# Filter-13.net
KiCad netlist of a schematic drawn in Altium Designer
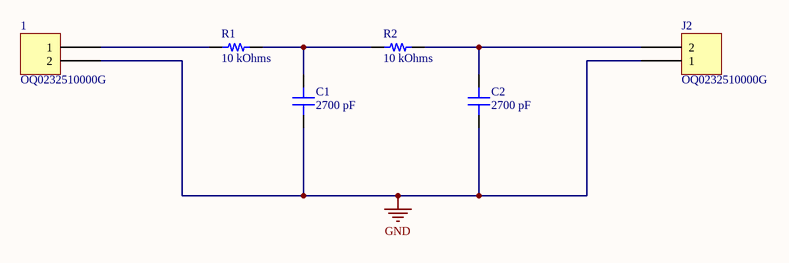
[diagram p0: Filter-13.SchDoc]

(export (version "E")
  (design (tool "Eeschema 10.0.6"))
  (components
    (comp (ref "1")
      (value "OQ0232510000G")
      (footprint "FCI 06-381-2PIN")
      (description "TERM BLOCK HDR 2POS 90DEG 3.81MM")
      (fields (field (name "MANUFACTURER") "Amphenol Anytek"))
      (libsource (lib "") (part "2 Pin_1"))
    )
    (comp (ref "C1")
      (value "2700 pF")
      (footprint "CAP 0603_1608")
      (description "CAP CER 2700PF 25V NP0 0603")
      (fields (field (name "PART NUMBER") "C0603C272F3GAC7867") (field (name "MANUFACTURER") "KEMET"))
      (libsource (lib "Celestial Altium Library - altium_library") (part "Capacitor"))
    )
    (comp (ref "C2")
      (value "2700 pF")
      (footprint "CAP 0603_1608")
      (description "CAP CER 2700PF 25V NP0 0603")
      (fields (field (name "PART NUMBER") "C0603C272F3GAC7867") (field (name "MANUFACTURER") "KEMET"))
      (libsource (lib "Celestial Altium Library - altium_library") (part "Capacitor"))
    )
    (comp (ref "J2")
      (value "OQ0232510000G")
      (footprint "FCI 06-381-2PIN")
      (description "TERM BLOCK HDR 2POS 90DEG 3.81MM")
      (fields (field (name "MANUFACTURER") "Amphenol Anytek"))
      (libsource (lib "Celestial Altium Library - altium_library") (part "2 Pin"))
    )
    (comp (ref "R1")
      (value "10 kOhms")
      (footprint "RES 0603_1608")
      (description "RES 10K OHM 0.1% 1/16W 0603")
      (fields
        (field (name "PART NUMBER") "RNCS0603BKE10K0")
        (field (name "MANUFACTURER") "Stackpole Electronics Inc")
      )
      (libsource (lib "Celestial Altium Library - altium_library") (part "Resistor"))
    )
    (comp (ref "R2")
      (value "10 kOhms")
      (footprint "RES 0603_1608")
      (description "RES 10K OHM 0.1% 1/16W 0603")
      (fields
        (field (name "PART NUMBER") "RNCS0603BKE10K0")
        (field (name "MANUFACTURER") "Stackpole Electronics Inc")
      )
      (libsource (lib "Celestial Altium Library - altium_library") (part "Resistor"))
    )
  )
  (nets
    (net (code "1") (name "GND") (class "Default")
      (node (ref "1") (pin "2") (pinfunction "2_2") (pintype "passive"))
      (node (ref "C1") (pin "1") (pinfunction "1_1") (pintype "passive"))
      (node (ref "C2") (pin "1") (pinfunction "1_1") (pintype "passive"))
      (node (ref "J2") (pin "1") (pinfunction "1_1") (pintype "passive"))
    )
    (net (code "2") (name "Net-(1-Pad1)") (class "Default")
      (node (ref "1") (pin "1") (pinfunction "1_1") (pintype "passive"))
      (node (ref "R1") (pin "1") (pinfunction "1_1") (pintype "passive"))
    )
    (net (code "3") (name "Net-(C1-Pad2)") (class "Default")
      (node (ref "C1") (pin "2") (pinfunction "2_2") (pintype "passive"))
      (node (ref "R1") (pin "2") (pinfunction "2_2") (pintype "passive"))
      (node (ref "R2") (pin "1") (pinfunction "1_1") (pintype "passive"))
    )
    (net (code "4") (name "Net-(C2-Pad2)") (class "Default")
      (node (ref "C2") (pin "2") (pinfunction "2_2") (pintype "passive"))
      (node (ref "J2") (pin "2") (pinfunction "2_2") (pintype "passive"))
      (node (ref "R2") (pin "2") (pinfunction "2_2") (pintype "passive"))
    )
  )
)
